# WiiCam.net
KiCad netlist of a schematic drawn in EAGLE
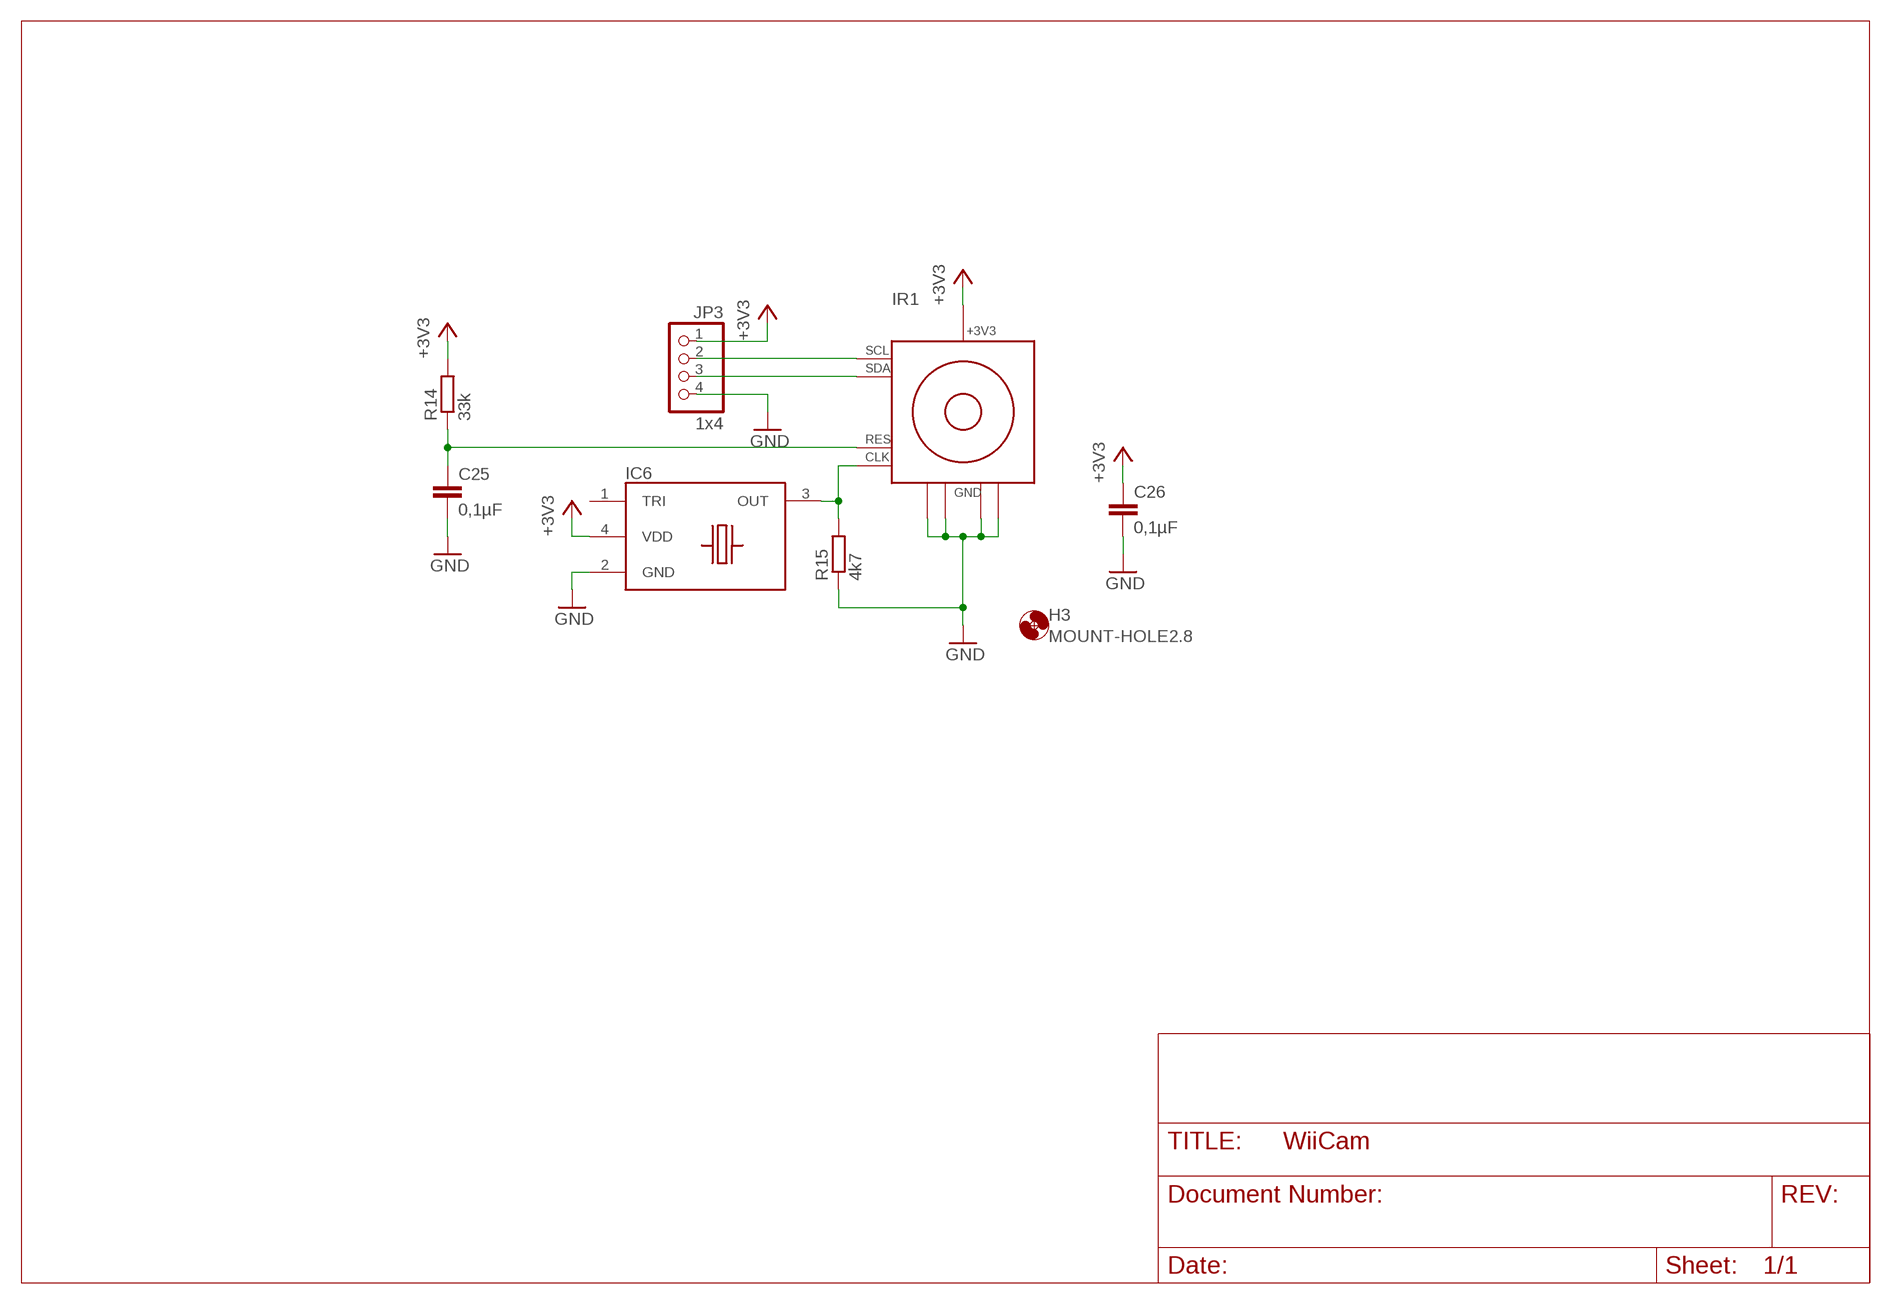
[diagram p0: schematic, sheet 1]

(export (version "E")
  (design (tool "Eeschema 10.0.6"))
  (components
    (comp (ref "C25")
      (value "0,1µF")
      (footprint "eagle-import:C0805")
      (libsource (lib "eagle-import") (part "C-EUC0805"))
    )
    (comp (ref "C26")
      (value "0,1µF")
      (footprint "eagle-import:C0805")
      (libsource (lib "eagle-import") (part "C-EUC0805"))
    )
    (comp (ref "H3")
      (value "MOUNT-HOLE2.8")
      (footprint "eagle-import:2,8")
      (libsource (lib "eagle-import") (part "MOUNT-HOLE2.8"))
    )
    (comp (ref "IC6")
      (value "7W-25.000MBB-T")
      (footprint "eagle-import:SMD_7X5MM")
      (libsource (lib "eagle-import") (part "TXC_7W"))
    )
    (comp (ref "IR1")
      (value "OWN_WII_IR_SENSOR")
      (footprint "eagle-import:OWN_WII_IR_SENSOR")
      (libsource (lib "eagle-import") (part "OWN_WII_IR_SENSOR"))
    )
    (comp (ref "JP3")
      (value "1x4")
      (footprint "eagle-import:1X04")
      (libsource (lib "eagle-import") (part "PINHD-1X4"))
    )
    (comp (ref "R14")
      (value "33k")
      (footprint "eagle-import:R0805")
      (libsource (lib "eagle-import") (part "R-EU_R0805"))
    )
    (comp (ref "R15")
      (value "4k7")
      (footprint "eagle-import:R0805")
      (libsource (lib "eagle-import") (part "R-EU_R0805"))
    )
  )
  (nets
    (net (code "1") (name "+3V3") (class "Default")
      (node (ref "C26") (pin "1") (pinfunction "1_1") (pintype "passive"))
      (node (ref "IC6") (pin "4") (pinfunction "VDD_4") (pintype "power_in"))
      (node (ref "IR1") (pin "1_+3V3") (pinfunction "+3V3_1_+3V3") (pintype "bidirectional"))
      (node (ref "JP3") (pin "1") (pinfunction "1_1") (pintype "passive"))
      (node (ref "R14") (pin "2") (pinfunction "2_2") (pintype "passive"))
    )
    (net (code "2") (name "GND") (class "Default")
      (node (ref "C25") (pin "2") (pinfunction "2_2") (pintype "passive"))
      (node (ref "C26") (pin "2") (pinfunction "2_2") (pintype "passive"))
      (node (ref "IC6") (pin "2") (pinfunction "GND_2") (pintype "power_in"))
      (node (ref "IR1") (pin "2_GND@1") (pinfunction "GND_2_GND@1") (pintype "bidirectional"))
      (node (ref "IR1") (pin "3_GND@2") (pinfunction "GND_3_GND@2") (pintype "bidirectional"))
      (node (ref "IR1") (pin "GND@3") (pinfunction "GND_GND@3") (pintype "bidirectional"))
      (node (ref "IR1") (pin "GND@4") (pinfunction "GND_GND@4") (pintype "bidirectional"))
      (node (ref "JP3") (pin "4") (pinfunction "4_4") (pintype "passive"))
      (node (ref "R15") (pin "1") (pinfunction "1_1") (pintype "passive"))
    )
    (net (code "3") (name "Net-(IC6-OUT)") (class "Default")
      (node (ref "IC6") (pin "3") (pinfunction "OUT_3") (pintype "output"))
      (node (ref "IR1") (pin "7_CLK") (pinfunction "CLK_7_CLK") (pintype "bidirectional"))
      (node (ref "R15") (pin "2") (pinfunction "2_2") (pintype "passive"))
    )
    (net (code "4") (name "Net-(IR1-RES)") (class "Default")
      (node (ref "C25") (pin "1") (pinfunction "1_1") (pintype "passive"))
      (node (ref "IR1") (pin "8_RESET") (pinfunction "RES_8_RESET") (pintype "bidirectional"))
      (node (ref "R14") (pin "1") (pinfunction "1_1") (pintype "passive"))
    )
    (net (code "5") (name "Net-(IR1-SCL)") (class "Default")
      (node (ref "IR1") (pin "5_SCL") (pinfunction "SCL_5_SCL") (pintype "bidirectional"))
      (node (ref "JP3") (pin "2") (pinfunction "2_2") (pintype "passive"))
    )
    (net (code "6") (name "Net-(IR1-SDA)") (class "Default")
      (node (ref "IR1") (pin "6_SDA") (pinfunction "SDA_6_SDA") (pintype "bidirectional"))
      (node (ref "JP3") (pin "3") (pinfunction "3_3") (pintype "passive"))
    )
    (net (code "7") (name "unconnected-(IC6-TRI-Pad1)") (class "Default")
      (node (ref "IC6") (pin "1") (pinfunction "TRI_1") (pintype "bidirectional"))
    )
  )
)
